# Sport_Analyzer_Chronojump_Teensy_4_4_but.net
KiCad netlist of a schematic drawn in EAGLE
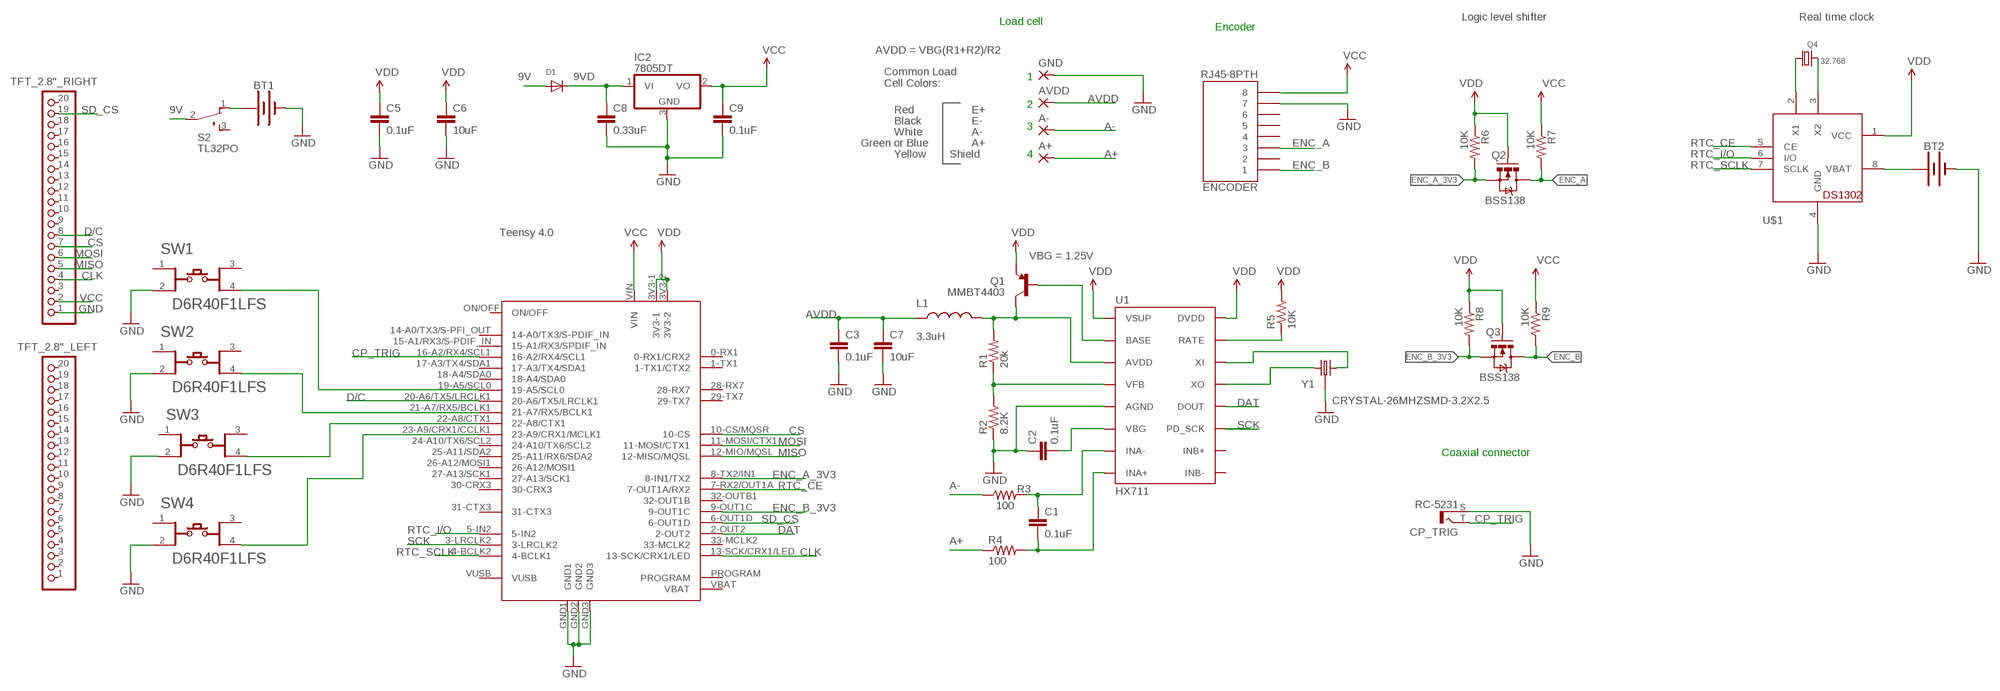
[diagram p0: schematic, sheet 1]

(export (version "E")
  (design (tool "Eeschema 10.0.6"))
  (components
    (comp (ref "A+")
      (value "3,81/1,4")
      (footprint "eagle-import:3,81_1,4")
      (libsource (lib "eagle-import") (part "3,81/1,4"))
    )
    (comp (ref "A-")
      (value "3,81/1,4")
      (footprint "eagle-import:3,81_1,4")
      (libsource (lib "eagle-import") (part "3,81/1,4"))
    )
    (comp (ref "AVDD")
      (value "3,81/1,4")
      (footprint "eagle-import:3,81_1,4")
      (libsource (lib "eagle-import") (part "3,81/1,4"))
    )
    (comp (ref "BT1")
      (value "BATTERY-9V")
      (footprint "eagle-import:BATTCON_9V")
      (libsource (lib "eagle-import") (part "BATTERY-9V"))
    )
    (comp (ref "BT2")
      (value "BATTERY-12MM_SMD")
      (footprint "eagle-import:BATTCON_12MM")
      (libsource (lib "eagle-import") (part "BATTERY-12MM_SMD"))
    )
    (comp (ref "C1")
      (value "0.1uF")
      (footprint "eagle-import:0603-CAP")
      (libsource (lib "eagle-import") (part "0.1UF-25V-5%(0603)"))
    )
    (comp (ref "C2")
      (value "0.1uF")
      (footprint "eagle-import:0603-CAP")
      (libsource (lib "eagle-import") (part "0.1UF-25V-5%(0603)"))
    )
    (comp (ref "C3")
      (value "0.1uF")
      (footprint "eagle-import:0603-CAP")
      (libsource (lib "eagle-import") (part "0.1UF-25V-5%(0603)"))
    )
    (comp (ref "C5")
      (value "0.1uF")
      (footprint "eagle-import:0603-CAP")
      (libsource (lib "eagle-import") (part "0.1UF-25V-5%(0603)"))
    )
    (comp (ref "C6")
      (value "10uF")
      (footprint "eagle-import:1210")
      (libsource (lib "eagle-import") (part "10UF50V20%(1210)"))
    )
    (comp (ref "C7")
      (value "10uF")
      (footprint "eagle-import:1210")
      (libsource (lib "eagle-import") (part "10UF50V20%(1210)"))
    )
    (comp (ref "C8")
      (value "0.33uF")
      (footprint "eagle-import:0603-CAP")
      (libsource (lib "eagle-import") (part "0.1UF-25V-5%(0603)"))
    )
    (comp (ref "C9")
      (value "0.1uF")
      (footprint "eagle-import:0603-CAP")
      (libsource (lib "eagle-import") (part "0.1UF-25V-5%(0603)"))
    )
    (comp (ref "CP_TRIG")
      (value "RC-5231")
      (footprint "eagle-import:RC-5231")
      (libsource (lib "eagle-import") (part "RC-5231"))
    )
    (comp (ref "D1")
      (value "DIODESOD-123")
      (footprint "eagle-import:SOD-123")
      (libsource (lib "eagle-import") (part "DIODESOD-123"))
    )
    (comp (ref "ENCODER")
      (value "RJ45-8PTH")
      (footprint "eagle-import:RJ45-8")
      (libsource (lib "eagle-import") (part "RJ45-8PTH"))
    )
    (comp (ref "GND")
      (value "3,81/1,4")
      (footprint "eagle-import:3,81_1,4")
      (libsource (lib "eagle-import") (part "3,81/1,4"))
    )
    (comp (ref "IC2")
      (value "7805DT")
      (footprint "eagle-import:TO252")
      (libsource (lib "eagle-import") (part "78DT05"))
    )
    (comp (ref "L1")
      (value "3.3uH")
      (footprint "eagle-import:0805")
      (libsource (lib "eagle-import") (part "INDUCTOR0805-IND"))
    )
    (comp (ref "Q1")
      (value "MMBT4403")
      (footprint "eagle-import:SOT23-3")
      (libsource (lib "eagle-import") (part "TRANSISTOR_PNPMMBT4403"))
    )
    (comp (ref "Q2")
      (value "BSS138")
      (footprint "eagle-import:SOT23-3")
      (libsource (lib "eagle-import") (part "MOSFET-NCHANNELSMD"))
    )
    (comp (ref "Q3")
      (value "BSS138")
      (footprint "eagle-import:SOT23-3")
      (libsource (lib "eagle-import") (part "MOSFET-NCHANNELSMD"))
    )
    (comp (ref "Q4")
      (value "32.768")
      (footprint "eagle-import:CRYSTAL_8X3.8")
      (libsource (lib "eagle-import") (part "CRYSTAL8.0X3.8"))
    )
    (comp (ref "R1")
      (value "20k")
      (footprint "eagle-import:0603-RES")
      (libsource (lib "eagle-import") (part "20KOHM1/10W1%(0603)"))
    )
    (comp (ref "R2")
      (value "8.2K")
      (footprint "eagle-import:0603-RES")
      (libsource (lib "eagle-import") (part "8.2KOHM-1/10W-5%(0603)"))
    )
    (comp (ref "R3")
      (value "100")
      (footprint "eagle-import:0603-RES")
      (libsource (lib "eagle-import") (part "100OHM-1/10W-1%(0603)"))
    )
    (comp (ref "R4")
      (value "100")
      (footprint "eagle-import:0603-RES")
      (libsource (lib "eagle-import") (part "100OHM-1/10W-1%(0603)"))
    )
    (comp (ref "R5")
      (value "10K")
      (footprint "eagle-import:0603-RES")
      (libsource (lib "eagle-import") (part "10KOHM-1/10W-1%(0603)0603"))
    )
    (comp (ref "R6")
      (value "10K")
      (footprint "eagle-import:0603-RES")
      (libsource (lib "eagle-import") (part "RESISTOR0603-RES"))
    )
    (comp (ref "R7")
      (value "10K")
      (footprint "eagle-import:0603-RES")
      (libsource (lib "eagle-import") (part "RESISTOR0603-RES"))
    )
    (comp (ref "R8")
      (value "10K")
      (footprint "eagle-import:0603-RES")
      (libsource (lib "eagle-import") (part "RESISTOR0603-RES"))
    )
    (comp (ref "R9")
      (value "10K")
      (footprint "eagle-import:0603-RES")
      (libsource (lib "eagle-import") (part "RESISTOR0603-RES"))
    )
    (comp (ref "S2")
      (value "TL32PO")
      (footprint "eagle-import:TL3XPO")
      (libsource (lib "eagle-import") (part "TL32PO"))
    )
    (comp (ref "SW1")
      (value "C&K_COMPONENTS_D6R40F1LFSC&K_COMPONENTS_D6R40F1LFS_0_0")
      (footprint "eagle-import:C&K_COMPONENTS_D6R40F1LFS_0")
      (fields
        (field (name "DIGIKEY_PART_NUMBER") "401-1975-ND")
        (field (name "MF") "C&K Components")
        (field (name "MOUSER_PART_NUMBER") "611-D6R40F1LFS")
      )
      (libsource (lib "eagle-import") (part "C&K_COMPONENTS_D6R40F1LFSC&K_COMPONENTS_D6R40F1LFS_0_0"))
    )
    (comp (ref "SW2")
      (value "C&K_COMPONENTS_D6R40F1LFSC&K_COMPONENTS_D6R40F1LFS_0_0")
      (footprint "eagle-import:C&K_COMPONENTS_D6R40F1LFS_0")
      (fields
        (field (name "DIGIKEY_PART_NUMBER") "401-1975-ND")
        (field (name "MF") "C&K Components")
        (field (name "MOUSER_PART_NUMBER") "611-D6R40F1LFS")
      )
      (libsource (lib "eagle-import") (part "C&K_COMPONENTS_D6R40F1LFSC&K_COMPONENTS_D6R40F1LFS_0_0"))
    )
    (comp (ref "SW3")
      (value "C&K_COMPONENTS_D6R40F1LFSC&K_COMPONENTS_D6R40F1LFS_0_0")
      (footprint "eagle-import:C&K_COMPONENTS_D6R40F1LFS_0")
      (fields
        (field (name "DIGIKEY_PART_NUMBER") "401-1975-ND")
        (field (name "MF") "C&K Components")
        (field (name "MOUSER_PART_NUMBER") "611-D6R40F1LFS")
      )
      (libsource (lib "eagle-import") (part "C&K_COMPONENTS_D6R40F1LFSC&K_COMPONENTS_D6R40F1LFS_0_0"))
    )
    (comp (ref "SW4")
      (value "C&K_COMPONENTS_D6R40F1LFSC&K_COMPONENTS_D6R40F1LFS_0_0")
      (footprint "eagle-import:C&K_COMPONENTS_D6R40F1LFS_0")
      (fields
        (field (name "DIGIKEY_PART_NUMBER") "401-1975-ND")
        (field (name "MF") "C&K Components")
        (field (name "MOUSER_PART_NUMBER") "611-D6R40F1LFS")
      )
      (libsource (lib "eagle-import") (part "C&K_COMPONENTS_D6R40F1LFSC&K_COMPONENTS_D6R40F1LFS_0_0"))
    )
    (comp (ref "TFT_2.8\"_LEFT")
      (value "PINHD-1X20")
      (footprint "eagle-import:1X20")
      (libsource (lib "eagle-import") (part "PINHD-1X20"))
    )
    (comp (ref "TFT_2.8\"_RIGHT")
      (value "PINHD-1X20")
      (footprint "eagle-import:1X20")
      (libsource (lib "eagle-import") (part "PINHD-1X20"))
    )
    (comp (ref "U$1")
      (value "DS1302")
      (footprint "eagle-import:DIL08-ROUND")
      (libsource (lib "eagle-import") (part "DS1302"))
    )
    (comp (ref "U$2")
      (value "TEENSY40")
      (footprint "eagle-import:TEENSY40")
      (libsource (lib "eagle-import") (part "TEENSY40"))
    )
    (comp (ref "U1")
      (value "HX711")
      (footprint "eagle-import:SO16")
      (libsource (lib "eagle-import") (part "HX711HX711"))
    )
    (comp (ref "Y1")
      (value "CRYSTAL-26MHZSMD-3.2X2.5")
      (footprint "eagle-import:CRYSTAL-SMD-3.2X2.5MM")
      (libsource (lib "eagle-import") (part "CRYSTAL-26MHZSMD-3.2X2.5"))
    )
  )
  (nets
    (net (code "1") (name "/9V") (class "Default")
      (node (ref "D1") (pin "A") (pinfunction "A_A") (pintype "passive"))
      (node (ref "S2") (pin "2") (pinfunction "P_2") (pintype "passive"))
    )
    (net (code "2") (name "/9VD") (class "Default")
      (node (ref "C8") (pin "1") (pinfunction "1_1") (pintype "passive"))
      (node (ref "D1") (pin "C") (pinfunction "C_C") (pintype "passive"))
      (node (ref "IC2") (pin "1") (pinfunction "VI_1") (pintype "input"))
    )
    (net (code "3") (name "/A+") (class "Default")
      (node (ref "A+") (pin "1") (pinfunction "P_1") (pintype "passive"))
      (node (ref "R4") (pin "1") (pinfunction "1_1") (pintype "passive"))
    )
    (net (code "4") (name "/A-") (class "Default")
      (node (ref "A-") (pin "1") (pinfunction "P_1") (pintype "passive"))
      (node (ref "R3") (pin "1") (pinfunction "1_1") (pintype "passive"))
    )
    (net (code "5") (name "/AVDD") (class "Default")
      (node (ref "AVDD") (pin "1") (pinfunction "P_1") (pintype "passive"))
      (node (ref "C3") (pin "1") (pinfunction "1_1") (pintype "passive"))
      (node (ref "C7") (pin "1") (pinfunction "1_1") (pintype "passive"))
      (node (ref "L1") (pin "1") (pinfunction "1_1") (pintype "passive"))
    )
    (net (code "6") (name "/CLK") (class "Default")
      (node (ref "TFT_2.8\"_RIGHT") (pin "4") (pinfunction "4_4") (pintype "passive"))
      (node (ref "U$2") (pin "13-SCK/CRX1/LED") (pinfunction "13-SCK/CRX1/LED_13-SCK/CRX1/LED") (pintype "bidirectional"))
    )
    (net (code "7") (name "/CP_TRIG") (class "Default")
      (node (ref "CP_TRIG") (pin "T") (pinfunction "T_T") (pintype "passive"))
      (node (ref "U$2") (pin "16-A2/RX4/SCL1") (pinfunction "16-A2/RX4/SCL1_16-A2/RX4/SCL1") (pintype "bidirectional"))
    )
    (net (code "8") (name "/CS") (class "Default")
      (node (ref "TFT_2.8\"_RIGHT") (pin "7") (pinfunction "7_7") (pintype "passive"))
      (node (ref "U$2") (pin "10-CS/MQSR") (pinfunction "10-CS_10-CS/MQSR") (pintype "bidirectional"))
    )
    (net (code "9") (name "/DAT") (class "Default")
      (node (ref "U$2") (pin "2-OUT2") (pinfunction "2-OUT2_2-OUT2") (pintype "bidirectional"))
      (node (ref "U1") (pin "12") (pinfunction "DOUT_12") (pintype "bidirectional"))
    )
    (net (code "10") (name "/D{slash}C") (class "Default")
      (node (ref "TFT_2.8\"_RIGHT") (pin "8") (pinfunction "8_8") (pintype "passive"))
      (node (ref "U$2") (pin "20-A6/TX5/LRCLK1") (pinfunction "20-A6/TX5/LRCLK1_20-A6/TX5/LRCLK1") (pintype "bidirectional"))
    )
    (net (code "11") (name "/MISO") (class "Default")
      (node (ref "TFT_2.8\"_RIGHT") (pin "5") (pinfunction "5_5") (pintype "passive"))
      (node (ref "U$2") (pin "12-MIO/MQSL") (pinfunction "12-MISO/MQSL_12-MIO/MQSL") (pintype "bidirectional"))
    )
    (net (code "12") (name "/MOSI") (class "Default")
      (node (ref "TFT_2.8\"_RIGHT") (pin "6") (pinfunction "6_6") (pintype "passive"))
      (node (ref "U$2") (pin "11-MOSI/CTX1") (pinfunction "11-MOSI/CTX1_11-MOSI/CTX1") (pintype "bidirectional"))
    )
    (net (code "13") (name "/RTC_CE") (class "Default")
      (node (ref "U$1") (pin "5") (pinfunction "CE_5") (pintype "input"))
      (node (ref "U$2") (pin "7-RX2/OUT1A") (pinfunction "7-OUT1A/RX2_7-RX2/OUT1A") (pintype "bidirectional"))
    )
    (net (code "14") (name "/RTC_I{slash}O") (class "Default")
      (node (ref "U$1") (pin "6") (pinfunction "I/O_6") (pintype "bidirectional"))
      (node (ref "U$2") (pin "5-IN2") (pinfunction "5-IN2_5-IN2") (pintype "bidirectional"))
    )
    (net (code "15") (name "/RTC_SCLK") (class "Default")
      (node (ref "U$1") (pin "7") (pinfunction "SCLK_7") (pintype "input"))
      (node (ref "U$2") (pin "4-BCLK2") (pinfunction "4-BCLK1_4-BCLK2") (pintype "bidirectional"))
    )
    (net (code "16") (name "/SCK") (class "Default")
      (node (ref "U$2") (pin "3-LRCLK2") (pinfunction "3-LRCLK2_3-LRCLK2") (pintype "bidirectional"))
      (node (ref "U1") (pin "11") (pinfunction "PD_SCK_11") (pintype "bidirectional"))
    )
    (net (code "17") (name "/SD_CS") (class "Default")
      (node (ref "TFT_2.8\"_RIGHT") (pin "19") (pinfunction "19_19") (pintype "passive"))
      (node (ref "U$2") (pin "6-OUT1D") (pinfunction "6-OUT1D_6-OUT1D") (pintype "bidirectional"))
    )
    (net (code "18") (name "ENC_A") (class "Default")
      (node (ref "ENCODER") (pin "3") (pinfunction "3_3") (pintype "bidirectional"))
      (node (ref "Q2") (pin "3") (pinfunction "D_3") (pintype "passive"))
      (node (ref "R7") (pin "2") (pinfunction "2_2") (pintype "passive"))
    )
    (net (code "19") (name "ENC_A_3V3") (class "Default")
      (node (ref "Q2") (pin "2") (pinfunction "S_2") (pintype "passive"))
      (node (ref "R6") (pin "2") (pinfunction "2_2") (pintype "passive"))
      (node (ref "U$2") (pin "8-TX2/IN1") (pinfunction "8-IN1/TX2_8-TX2/IN1") (pintype "bidirectional"))
    )
    (net (code "20") (name "ENC_B") (class "Default")
      (node (ref "ENCODER") (pin "1") (pinfunction "1_1") (pintype "bidirectional"))
      (node (ref "Q3") (pin "3") (pinfunction "D_3") (pintype "passive"))
      (node (ref "R9") (pin "2") (pinfunction "2_2") (pintype "passive"))
    )
    (net (code "21") (name "ENC_B_3V3") (class "Default")
      (node (ref "Q3") (pin "2") (pinfunction "S_2") (pintype "passive"))
      (node (ref "R8") (pin "2") (pinfunction "2_2") (pintype "passive"))
      (node (ref "U$2") (pin "9-OUT1C") (pinfunction "9-OUT1C_9-OUT1C") (pintype "bidirectional"))
    )
    (net (code "22") (name "GND") (class "Default")
      (node (ref "BT1") (pin "-") (pinfunction "-_-") (pintype "power_in"))
      (node (ref "BT2") (pin "GND") (pinfunction "-_GND") (pintype "power_in"))
      (node (ref "C2") (pin "1") (pinfunction "1_1") (pintype "passive"))
      (node (ref "C3") (pin "2") (pinfunction "2_2") (pintype "passive"))
      (node (ref "C5") (pin "2") (pinfunction "2_2") (pintype "passive"))
      (node (ref "C6") (pin "2") (pinfunction "2_2") (pintype "passive"))
      (node (ref "C7") (pin "2") (pinfunction "2_2") (pintype "passive"))
      (node (ref "C8") (pin "2") (pinfunction "2_2") (pintype "passive"))
      (node (ref "C9") (pin "2") (pinfunction "2_2") (pintype "passive"))
      (node (ref "CP_TRIG") (pin "S") (pinfunction "S_S") (pintype "passive"))
      (node (ref "ENCODER") (pin "7") (pinfunction "7_7") (pintype "bidirectional"))
      (node (ref "GND") (pin "1") (pinfunction "P_1") (pintype "passive"))
      (node (ref "IC2") (pin "3") (pinfunction "GND_3") (pintype "passive"))
      (node (ref "R2") (pin "1") (pinfunction "1_1") (pintype "passive"))
      (node (ref "SW1") (pin "2") (pinfunction "2_2") (pintype "passive"))
      (node (ref "SW2") (pin "2") (pinfunction "2_2") (pintype "passive"))
      (node (ref "SW3") (pin "2") (pinfunction "2_2") (pintype "passive"))
      (node (ref "SW4") (pin "2") (pinfunction "2_2") (pintype "passive"))
      (node (ref "TFT_2.8\"_RIGHT") (pin "1") (pinfunction "1_1") (pintype "passive"))
      (node (ref "U$1") (pin "4") (pinfunction "GND_4") (pintype "power_in"))
      (node (ref "U$2") (pin "GND1") (pinfunction "GND1_GND1") (pintype "bidirectional"))
      (node (ref "U$2") (pin "GND2") (pinfunction "GND2_GND2") (pintype "bidirectional"))
      (node (ref "U$2") (pin "GND3") (pinfunction "GND3_GND3") (pintype "bidirectional"))
      (node (ref "U1") (pin "5") (pinfunction "AGND_5") (pintype "bidirectional"))
      (node (ref "Y1") (pin "2") (pinfunction "GND_2") (pintype "power_in"))
      (node (ref "Y1") (pin "4") (pinfunction "GND_4") (pintype "power_in"))
    )
    (net (code "23") (name "Net-(BT2-+)") (class "Default")
      (node (ref "BT2") (pin "PWR@1") (pinfunction "+_PWR@1") (pintype "power_in"))
      (node (ref "U$1") (pin "8") (pinfunction "VBAT_8") (pintype "power_in"))
    )
    (net (code "24") (name "Net-(Q1-B)") (class "Default")
      (node (ref "Q1") (pin "1") (pinfunction "B_1") (pintype "passive"))
      (node (ref "U1") (pin "2") (pinfunction "BASE_2") (pintype "bidirectional"))
    )
    (net (code "25") (name "Net-(Q1-C)") (class "Default")
      (node (ref "L1") (pin "2") (pinfunction "2_2") (pintype "passive"))
      (node (ref "Q1") (pin "3") (pinfunction "C_3") (pintype "passive"))
      (node (ref "R1") (pin "2") (pinfunction "2_2") (pintype "passive"))
      (node (ref "U1") (pin "3") (pinfunction "AVDD_3") (pintype "bidirectional"))
    )
    (net (code "26") (name "Net-(Q4-1)") (class "Default")
      (node (ref "Q4") (pin "P$1") (pinfunction "1_P$1") (pintype "passive"))
      (node (ref "U$1") (pin "3") (pinfunction "X2_3") (pintype "passive"))
    )
    (net (code "27") (name "Net-(Q4-2)") (class "Default")
      (node (ref "Q4") (pin "P$4") (pinfunction "2_P$4") (pintype "passive"))
      (node (ref "U$1") (pin "2") (pinfunction "X1_2") (pintype "passive"))
    )
    (net (code "28") (name "Net-(S2-O)") (class "Default")
      (node (ref "BT1") (pin "+") (pinfunction "+_+") (pintype "power_in"))
      (node (ref "S2") (pin "1") (pinfunction "O_1") (pintype "passive"))
    )
    (net (code "29") (name "Net-(SW1-Pad4)") (class "Default")
      (node (ref "SW1") (pin "4") (pinfunction "4_4") (pintype "passive"))
      (node (ref "U$2") (pin "19-A5/SCL0") (pinfunction "19-A5/SCL0_19-A5/SCL0") (pintype "bidirectional"))
    )
    (net (code "30") (name "Net-(SW2-Pad4)") (class "Default")
      (node (ref "SW2") (pin "4") (pinfunction "4_4") (pintype "passive"))
      (node (ref "U$2") (pin "21-A7/RX5/BCLK1") (pinfunction "21-A7/RX5/BCLK1_21-A7/RX5/BCLK1") (pintype "bidirectional"))
    )
    (net (code "31") (name "Net-(SW3-Pad4)") (class "Default")
      (node (ref "SW3") (pin "4") (pinfunction "4_4") (pintype "passive"))
      (node (ref "U$2") (pin "22-A8/CTX1") (pinfunction "22-A8/CTX1_22-A8/CTX1") (pintype "bidirectional"))
    )
    (net (code "32") (name "Net-(U$2-23-A9{slash}CRX1{slash}MCLK1)") (class "Default")
      (node (ref "SW4") (pin "4") (pinfunction "4_4") (pintype "passive"))
      (node (ref "U$2") (pin "23-A9/CRX1/CCLK1") (pinfunction "23-A9/CRX1/MCLK1_23-A9/CRX1/CCLK1") (pintype "bidirectional"))
    )
    (net (code "33") (name "Net-(U1-INA+)") (class "Default")
      (node (ref "C1") (pin "2") (pinfunction "2_2") (pintype "passive"))
      (node (ref "R4") (pin "2") (pinfunction "2_2") (pintype "passive"))
      (node (ref "U1") (pin "8") (pinfunction "INA+_8") (pintype "bidirectional"))
    )
    (net (code "34") (name "Net-(U1-INA-)") (class "Default")
      (node (ref "C1") (pin "1") (pinfunction "1_1") (pintype "passive"))
      (node (ref "R3") (pin "2") (pinfunction "2_2") (pintype "passive"))
      (node (ref "U1") (pin "7") (pinfunction "INA-_7") (pintype "bidirectional"))
    )
    (net (code "35") (name "Net-(U1-RATE)") (class "Default")
      (node (ref "R5") (pin "1") (pinfunction "1_1") (pintype "passive"))
      (node (ref "U1") (pin "15") (pinfunction "RATE_15") (pintype "bidirectional"))
    )
    (net (code "36") (name "Net-(U1-VBG)") (class "Default")
      (node (ref "C2") (pin "2") (pinfunction "2_2") (pintype "passive"))
      (node (ref "U1") (pin "6") (pinfunction "VBG_6") (pintype "bidirectional"))
    )
    (net (code "37") (name "Net-(U1-VFB)") (class "Default")
      (node (ref "R1") (pin "1") (pinfunction "1_1") (pintype "passive"))
      (node (ref "R2") (pin "2") (pinfunction "2_2") (pintype "passive"))
      (node (ref "U1") (pin "4") (pinfunction "VFB_4") (pintype "bidirectional"))
    )
    (net (code "38") (name "Net-(U1-XI)") (class "Default")
      (node (ref "U1") (pin "14") (pinfunction "XI_14") (pintype "bidirectional"))
      (node (ref "Y1") (pin "3") (pinfunction "2_3") (pintype "passive"))
    )
    (net (code "39") (name "Net-(U1-XO)") (class "Default")
      (node (ref "U1") (pin "13") (pinfunction "XO_13") (pintype "bidirectional"))
      (node (ref "Y1") (pin "1") (pinfunction "1_1") (pintype "passive"))
    )
    (net (code "40") (name "VCC") (class "Default")
      (node (ref "C9") (pin "1") (pinfunction "1_1") (pintype "passive"))
      (node (ref "ENCODER") (pin "8") (pinfunction "8_8") (pintype "bidirectional"))
      (node (ref "IC2") (pin "2") (pinfunction "VO_2") (pintype "passive"))
      (node (ref "R7") (pin "1") (pinfunction "1_1") (pintype "passive"))
      (node (ref "R9") (pin "1") (pinfunction "1_1") (pintype "passive"))
      (node (ref "TFT_2.8\"_RIGHT") (pin "2") (pinfunction "2_2") (pintype "passive"))
      (node (ref "U$2") (pin "VIN") (pinfunction "VIN_VIN") (pintype "bidirectional"))
    )
    (net (code "41") (name "VDD") (class "Default")
      (node (ref "C5") (pin "1") (pinfunction "1_1") (pintype "passive"))
      (node (ref "C6") (pin "1") (pinfunction "1_1") (pintype "passive"))
      (node (ref "Q1") (pin "2") (pinfunction "E_2") (pintype "passive"))
      (node (ref "Q2") (pin "1") (pinfunction "G_1") (pintype "passive"))
      (node (ref "Q3") (pin "1") (pinfunction "G_1") (pintype "passive"))
      (node (ref "R5") (pin "2") (pinfunction "2_2") (pintype "passive"))
      (node (ref "R6") (pin "1") (pinfunction "1_1") (pintype "passive"))
      (node (ref "R8") (pin "1") (pinfunction "1_1") (pintype "passive"))
      (node (ref "U$1") (pin "1") (pinfunction "VCC_1") (pintype "power_in"))
      (node (ref "U$2") (pin "3V3-1") (pinfunction "3V3-1_3V3-1") (pintype "bidirectional"))
      (node (ref "U$2") (pin "3V3-2") (pinfunction "3V3-2_3V3-2") (pintype "bidirectional"))
      (node (ref "U1") (pin "1") (pinfunction "VSUP_1") (pintype "bidirectional"))
      (node (ref "U1") (pin "16") (pinfunction "DVDD_16") (pintype "bidirectional"))
    )
    (net (code "42") (name "unconnected-(ENCODER-Pad2)") (class "Default")
      (node (ref "ENCODER") (pin "2") (pinfunction "2_2") (pintype "bidirectional"))
    )
    (net (code "43") (name "unconnected-(ENCODER-Pad4)") (class "Default")
      (node (ref "ENCODER") (pin "4") (pinfunction "4_4") (pintype "bidirectional"))
    )
    (net (code "44") (name "unconnected-(ENCODER-Pad5)") (class "Default")
      (node (ref "ENCODER") (pin "5") (pinfunction "5_5") (pintype "bidirectional"))
    )
    (net (code "45") (name "unconnected-(ENCODER-Pad6)") (class "Default")
      (node (ref "ENCODER") (pin "6") (pinfunction "6_6") (pintype "bidirectional"))
    )
    (net (code "46") (name "unconnected-(S2-S-Pad3)") (class "Default")
      (node (ref "S2") (pin "3") (pinfunction "S_3") (pintype "passive"))
    )
    (net (code "47") (name "unconnected-(SW1-Pad1)") (class "Default")
      (node (ref "SW1") (pin "1") (pinfunction "1_1") (pintype "passive"))
    )
    (net (code "48") (name "unconnected-(SW1-Pad3)") (class "Default")
      (node (ref "SW1") (pin "3") (pinfunction "3_3") (pintype "passive"))
    )
    (net (code "49") (name "unconnected-(SW2-Pad1)") (class "Default")
      (node (ref "SW2") (pin "1") (pinfunction "1_1") (pintype "passive"))
    )
    (net (code "50") (name "unconnected-(SW2-Pad3)") (class "Default")
      (node (ref "SW2") (pin "3") (pinfunction "3_3") (pintype "passive"))
    )
    (net (code "51") (name "unconnected-(SW3-Pad1)") (class "Default")
      (node (ref "SW3") (pin "1") (pinfunction "1_1") (pintype "passive"))
    )
    (net (code "52") (name "unconnected-(SW3-Pad3)") (class "Default")
      (node (ref "SW3") (pin "3") (pinfunction "3_3") (pintype "passive"))
    )
    (net (code "53") (name "unconnected-(SW4-Pad1)") (class "Default")
      (node (ref "SW4") (pin "1") (pinfunction "1_1") (pintype "passive"))
    )
    (net (code "54") (name "unconnected-(SW4-Pad3)") (class "Default")
      (node (ref "SW4") (pin "3") (pinfunction "3_3") (pintype "passive"))
    )
    (net (code "55") (name "unconnected-(TFT_2.8\"_LEFT-Pad1)") (class "Default")
      (node (ref "TFT_2.8\"_LEFT") (pin "1") (pinfunction "1_1") (pintype "passive"))
    )
    (net (code "56") (name "unconnected-(TFT_2.8\"_LEFT-Pad2)") (class "Default")
      (node (ref "TFT_2.8\"_LEFT") (pin "2") (pinfunction "2_2") (pintype "passive"))
    )
    (net (code "57") (name "unconnected-(TFT_2.8\"_LEFT-Pad3)") (class "Default")
      (node (ref "TFT_2.8\"_LEFT") (pin "3") (pinfunction "3_3") (pintype "passive"))
    )
    (net (code "58") (name "unconnected-(TFT_2.8\"_LEFT-Pad4)") (class "Default")
      (node (ref "TFT_2.8\"_LEFT") (pin "4") (pinfunction "4_4") (pintype "passive"))
    )
    (net (code "59") (name "unconnected-(TFT_2.8\"_LEFT-Pad5)") (class "Default")
      (node (ref "TFT_2.8\"_LEFT") (pin "5") (pinfunction "5_5") (pintype "passive"))
    )
    (net (code "60") (name "unconnected-(TFT_2.8\"_LEFT-Pad6)") (class "Default")
      (node (ref "TFT_2.8\"_LEFT") (pin "6") (pinfunction "6_6") (pintype "passive"))
    )
    (net (code "61") (name "unconnected-(TFT_2.8\"_LEFT-Pad7)") (class "Default")
      (node (ref "TFT_2.8\"_LEFT") (pin "7") (pinfunction "7_7") (pintype "passive"))
    )
    (net (code "62") (name "unconnected-(TFT_2.8\"_LEFT-Pad8)") (class "Default")
      (node (ref "TFT_2.8\"_LEFT") (pin "8") (pinfunction "8_8") (pintype "passive"))
    )
    (net (code "63") (name "unconnected-(TFT_2.8\"_LEFT-Pad9)") (class "Default")
      (node (ref "TFT_2.8\"_LEFT") (pin "9") (pinfunction "9_9") (pintype "passive"))
    )
    (net (code "64") (name "unconnected-(TFT_2.8\"_LEFT-Pad10)") (class "Default")
      (node (ref "TFT_2.8\"_LEFT") (pin "10") (pinfunction "10_10") (pintype "passive"))
    )
    (net (code "65") (name "unconnected-(TFT_2.8\"_LEFT-Pad11)") (class "Default")
      (node (ref "TFT_2.8\"_LEFT") (pin "11") (pinfunction "11_11") (pintype "passive"))
    )
    (net (code "66") (name "unconnected-(TFT_2.8\"_LEFT-Pad12)") (class "Default")
      (node (ref "TFT_2.8\"_LEFT") (pin "12") (pinfunction "12_12") (pintype "passive"))
    )
    (net (code "67") (name "unconnected-(TFT_2.8\"_LEFT-Pad13)") (class "Default")
      (node (ref "TFT_2.8\"_LEFT") (pin "13") (pinfunction "13_13") (pintype "passive"))
    )
    (net (code "68") (name "unconnected-(TFT_2.8\"_LEFT-Pad14)") (class "Default")
      (node (ref "TFT_2.8\"_LEFT") (pin "14") (pinfunction "14_14") (pintype "passive"))
    )
    (net (code "69") (name "unconnected-(TFT_2.8\"_LEFT-Pad15)") (class "Default")
      (node (ref "TFT_2.8\"_LEFT") (pin "15") (pinfunction "15_15") (pintype "passive"))
    )
    (net (code "70") (name "unconnected-(TFT_2.8\"_LEFT-Pad16)") (class "Default")
      (node (ref "TFT_2.8\"_LEFT") (pin "16") (pinfunction "16_16") (pintype "passive"))
    )
    (net (code "71") (name "unconnected-(TFT_2.8\"_LEFT-Pad17)") (class "Default")
      (node (ref "TFT_2.8\"_LEFT") (pin "17") (pinfunction "17_17") (pintype "passive"))
    )
    (net (code "72") (name "unconnected-(TFT_2.8\"_LEFT-Pad18)") (class "Default")
      (node (ref "TFT_2.8\"_LEFT") (pin "18") (pinfunction "18_18") (pintype "passive"))
    )
    (net (code "73") (name "unconnected-(TFT_2.8\"_LEFT-Pad19)") (class "Default")
      (node (ref "TFT_2.8\"_LEFT") (pin "19") (pinfunction "19_19") (pintype "passive"))
    )
    (net (code "74") (name "unconnected-(TFT_2.8\"_LEFT-Pad20)") (class "Default")
      (node (ref "TFT_2.8\"_LEFT") (pin "20") (pinfunction "20_20") (pintype "passive"))
    )
    (net (code "75") (name "unconnected-(TFT_2.8\"_RIGHT-Pad3)") (class "Default")
      (node (ref "TFT_2.8\"_RIGHT") (pin "3") (pinfunction "3_3") (pintype "passive"))
    )
    (net (code "76") (name "unconnected-(TFT_2.8\"_RIGHT-Pad9)") (class "Default")
      (node (ref "TFT_2.8\"_RIGHT") (pin "9") (pinfunction "9_9") (pintype "passive"))
    )
    (net (code "77") (name "unconnected-(TFT_2.8\"_RIGHT-Pad10)") (class "Default")
      (node (ref "TFT_2.8\"_RIGHT") (pin "10") (pinfunction "10_10") (pintype "passive"))
    )
    (net (code "78") (name "unconnected-(TFT_2.8\"_RIGHT-Pad11)") (class "Default")
      (node (ref "TFT_2.8\"_RIGHT") (pin "11") (pinfunction "11_11") (pintype "passive"))
    )
    (net (code "79") (name "unconnected-(TFT_2.8\"_RIGHT-Pad12)") (class "Default")
      (node (ref "TFT_2.8\"_RIGHT") (pin "12") (pinfunction "12_12") (pintype "passive"))
    )
    (net (code "80") (name "unconnected-(TFT_2.8\"_RIGHT-Pad13)") (class "Default")
      (node (ref "TFT_2.8\"_RIGHT") (pin "13") (pinfunction "13_13") (pintype "passive"))
    )
    (net (code "81") (name "unconnected-(TFT_2.8\"_RIGHT-Pad14)") (class "Default")
      (node (ref "TFT_2.8\"_RIGHT") (pin "14") (pinfunction "14_14") (pintype "passive"))
    )
    (net (code "82") (name "unconnected-(TFT_2.8\"_RIGHT-Pad15)") (class "Default")
      (node (ref "TFT_2.8\"_RIGHT") (pin "15") (pinfunction "15_15") (pintype "passive"))
    )
    (net (code "83") (name "unconnected-(TFT_2.8\"_RIGHT-Pad16)") (class "Default")
      (node (ref "TFT_2.8\"_RIGHT") (pin "16") (pinfunction "16_16") (pintype "passive"))
    )
    (net (code "84") (name "unconnected-(TFT_2.8\"_RIGHT-Pad17)") (class "Default")
      (node (ref "TFT_2.8\"_RIGHT") (pin "17") (pinfunction "17_17") (pintype "passive"))
    )
    (net (code "85") (name "unconnected-(TFT_2.8\"_RIGHT-Pad18)") (class "Default")
      (node (ref "TFT_2.8\"_RIGHT") (pin "18") (pinfunction "18_18") (pintype "passive"))
    )
    (net (code "86") (name "unconnected-(TFT_2.8\"_RIGHT-Pad20)") (class "Default")
      (node (ref "TFT_2.8\"_RIGHT") (pin "20") (pinfunction "20_20") (pintype "passive"))
    )
    (net (code "87") (name "unconnected-(U$2-0-RX1{slash}CRX2-Pad0-RX1)") (class "Default")
      (node (ref "U$2") (pin "0-RX1") (pinfunction "0-RX1/CRX2_0-RX1") (pintype "bidirectional"))
    )
    (net (code "88") (name "unconnected-(U$2-1-TX1{slash}CTX2-Pad1-TX1)") (class "Default")
      (node (ref "U$2") (pin "1-TX1") (pinfunction "1-TX1/CTX2_1-TX1") (pintype "bidirectional"))
    )
    (net (code "89") (name "unconnected-(U$2-14-A0{slash}TX3{slash}S-PDIF_IN-Pad14-A0{slash}TX3{slash}S-PFI_OUT)") (class "Default")
      (node (ref "U$2") (pin "14-A0/TX3/S-PFI_OUT") (pinfunction "14-A0/TX3/S-PDIF_IN_14-A0/TX3/S-PFI_OUT") (pintype "bidirectional"))
    )
    (net (code "90") (name "unconnected-(U$2-15-A1{slash}RX3{slash}SPDIF_IN-Pad15-A1{slash}RX3{slash}S-PDIF_IN)") (class "Default")
      (node (ref "U$2") (pin "15-A1/RX3/S-PDIF_IN") (pinfunction "15-A1/RX3/SPDIF_IN_15-A1/RX3/S-PDIF_IN") (pintype "bidirectional"))
    )
    (net (code "91") (name "unconnected-(U$2-25-A11{slash}RX6{slash}SDA2-Pad25-A11{slash}SDA2)") (class "Default")
      (node (ref "U$2") (pin "25-A11/SDA2") (pinfunction "25-A11/RX6/SDA2_25-A11/SDA2") (pintype "bidirectional"))
    )
    (net (code "92") (name "unconnected-(U$2-32-OUT1B-Pad32-OUTB1)") (class "Default")
      (node (ref "U$2") (pin "32-OUTB1") (pinfunction "32-OUT1B_32-OUTB1") (pintype "bidirectional"))
    )
    (net (code "93") (name "unconnected-(U$2-Pad17-A3{slash}TX4{slash}SDA1)") (class "Default")
      (node (ref "U$2") (pin "17-A3/TX4/SDA1") (pinfunction "17-A3/TX4/SDA1_17-A3/TX4/SDA1") (pintype "bidirectional"))
    )
    (net (code "94") (name "unconnected-(U$2-Pad18-A4{slash}SDA0)") (class "Default")
      (node (ref "U$2") (pin "18-A4/SDA0") (pinfunction "18-A4/SDA0_18-A4/SDA0") (pintype "bidirectional"))
    )
    (net (code "95") (name "unconnected-(U$2-Pad24-A10{slash}TX6{slash}SCL2)") (class "Default")
      (node (ref "U$2") (pin "24-A10/TX6/SCL2") (pinfunction "24-A10/TX6/SCL2_24-A10/TX6/SCL2") (pintype "bidirectional"))
    )
    (net (code "96") (name "unconnected-(U$2-Pad26-A12{slash}MOSI1)") (class "Default")
      (node (ref "U$2") (pin "26-A12/MOSI1") (pinfunction "26-A12/MOSI1_26-A12/MOSI1") (pintype "bidirectional"))
    )
    (net (code "97") (name "unconnected-(U$2-Pad27-A13{slash}SCK1)") (class "Default")
      (node (ref "U$2") (pin "27-A13/SCK1") (pinfunction "27-A13/SCK1_27-A13/SCK1") (pintype "bidirectional"))
    )
    (net (code "98") (name "unconnected-(U$2-Pad28-RX7)") (class "Default")
      (node (ref "U$2") (pin "28-RX7") (pinfunction "28-RX7_28-RX7") (pintype "bidirectional"))
    )
    (net (code "99") (name "unconnected-(U$2-Pad29-TX7)") (class "Default")
      (node (ref "U$2") (pin "29-TX7") (pinfunction "29-TX7_29-TX7") (pintype "bidirectional"))
    )
    (net (code "100") (name "unconnected-(U$2-Pad30-CRX3)") (class "Default")
      (node (ref "U$2") (pin "30-CRX3") (pinfunction "30-CRX3_30-CRX3") (pintype "bidirectional"))
    )
    (net (code "101") (name "unconnected-(U$2-Pad31-CTX3)") (class "Default")
      (node (ref "U$2") (pin "31-CTX3") (pinfunction "31-CTX3_31-CTX3") (pintype "bidirectional"))
    )
    (net (code "102") (name "unconnected-(U$2-Pad33-MCLK2)") (class "Default")
      (node (ref "U$2") (pin "33-MCLK2") (pinfunction "33-MCLK2_33-MCLK2") (pintype "bidirectional"))
    )
    (net (code "103") (name "unconnected-(U$2-PadON{slash}OFF)") (class "Default")
      (node (ref "U$2") (pin "ON/OFF") (pinfunction "ON/OFF_ON/OFF") (pintype "bidirectional"))
    )
    (net (code "104") (name "unconnected-(U$2-PadPROGRAM)") (class "Default")
      (node (ref "U$2") (pin "PROGRAM") (pinfunction "PROGRAM_PROGRAM") (pintype "bidirectional"))
    )
    (net (code "105") (name "unconnected-(U$2-PadVBAT)") (class "Default")
      (node (ref "U$2") (pin "VBAT") (pinfunction "VBAT_VBAT") (pintype "bidirectional"))
    )
    (net (code "106") (name "unconnected-(U$2-PadVUSB)") (class "Default")
      (node (ref "U$2") (pin "VUSB") (pinfunction "VUSB_VUSB") (pintype "bidirectional"))
    )
    (net (code "107") (name "unconnected-(U1-INB+-Pad10)") (class "Default")
      (node (ref "U1") (pin "10") (pinfunction "INB+_10") (pintype "bidirectional"))
    )
    (net (code "108") (name "unconnected-(U1-INB--Pad9)") (class "Default")
      (node (ref "U1") (pin "9") (pinfunction "INB-_9") (pintype "bidirectional"))
    )
  )
)
